# Servo_PCB.net
KiCad netlist of a schematic drawn in Altium Designer
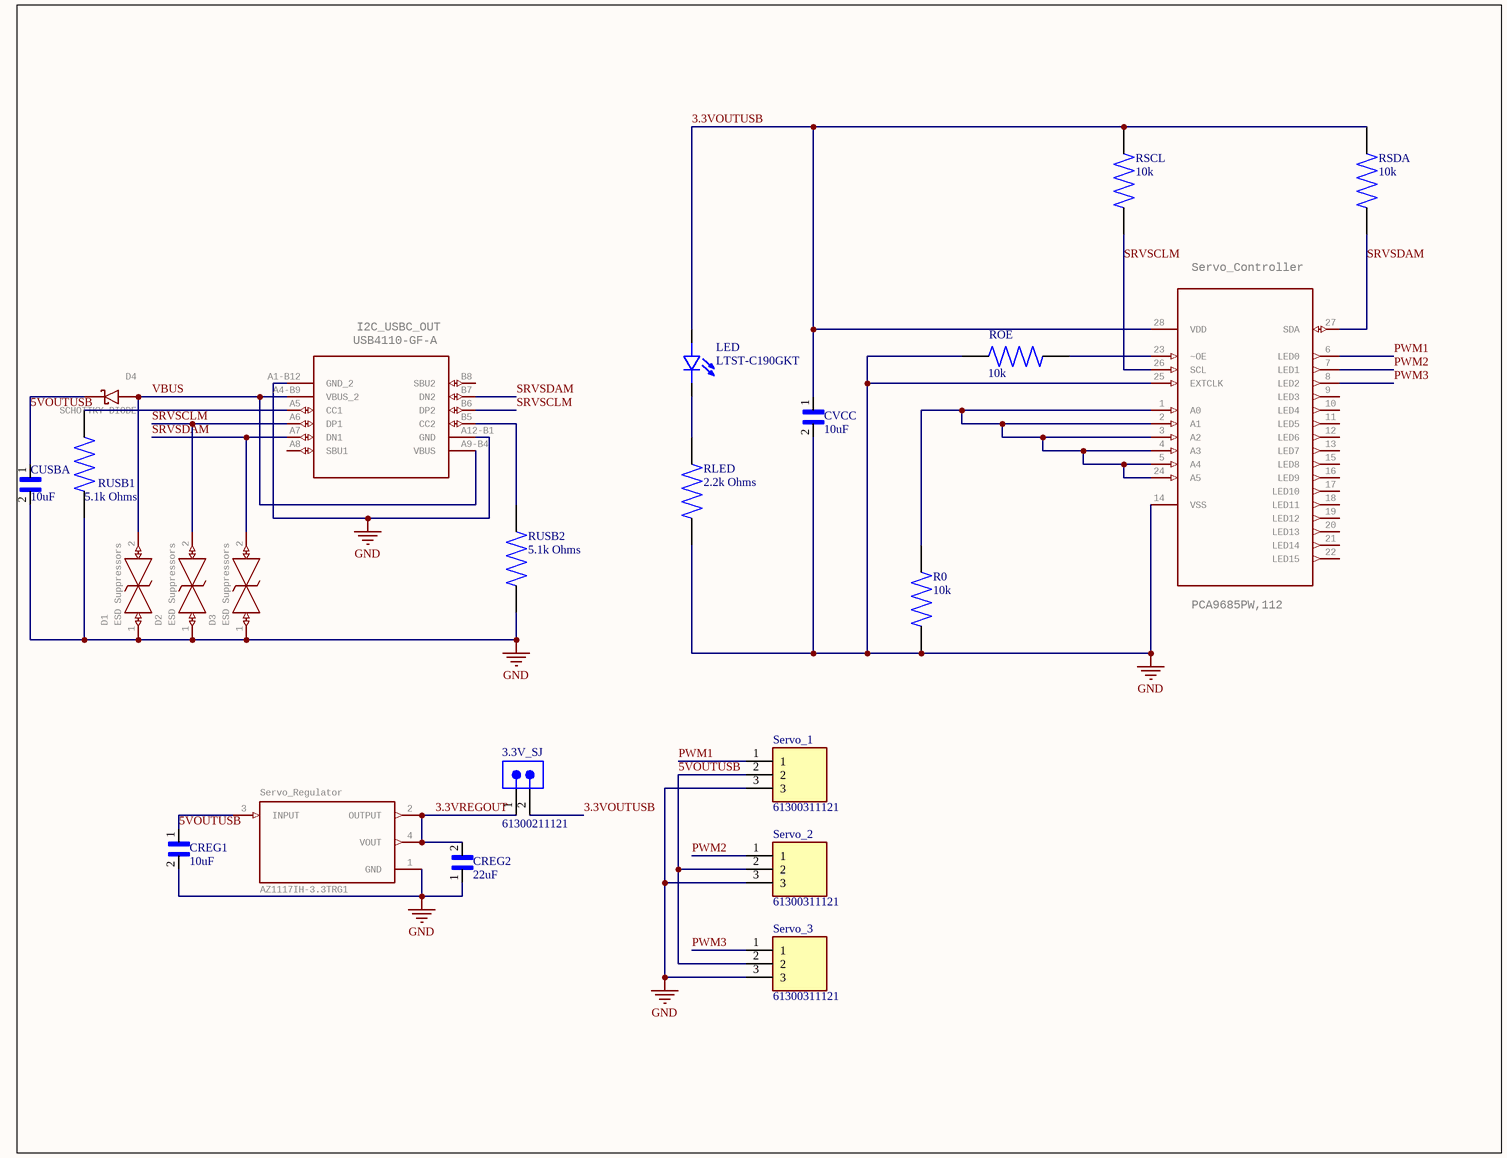
[diagram p0: Servo_PCB.SchDoc]

(export (version "E")
  (design (tool "Eeschema 10.0.6"))
  (components
    (comp (ref "3.3V_SJ")
      (value "61300211121")
      (footprint "61300211121")
      (description "CONN HEADER VERT 2POS 2.54MM")
      (libsource (lib "61300211121") (part "CMP-1712-00002-5"))
    )
    (comp (ref "CREG1")
      (value "10uF")
      (footprint "C0805C106J8RACAUTO.:CAPC2012X88N")
      (description "10ÂµF Â±5% 10V Ceramic Capacitor X7R 0805 _2012 Metric_")
      (fields (field (name "MP") "C0805C106J8RACAUTO") (field (name "MF") "KEMET"))
      (libsource (lib "C0805C106J8RACAUTO.") (part "C0805C106J8RACAUTO"))
    )
    (comp (ref "CREG2")
      (value "22uF")
      (footprint "GRM21BR61C226ME44L:CAPC2012X145N")
      (description "SMD Capacitor X5R(EIA) with Capacitance: 22uF Tol. 20%. Rated Voltage: 16Vdc")
      (fields (field (name "MP") "GRM21BR61C226ME44L") (field (name "MF") "Murata"))
      (libsource (lib "GRM21BR61C226ME44L") (part "GRM21BR61C226ME44L"))
    )
    (comp (ref "CUSBA")
      (value "10uF")
      (footprint "C0805C106J8RACAUTO.:CAPC2012X88N")
      (description "CAP CER 10UF 10V X7R 0805")
      (fields (field (name "MP") "C0805C106J8RACAUTO") (field (name "MF") "KEMET"))
      (libsource (lib "C0805C106J8RACAUTO.") (part "C0805C106J8RACAUTO"))
    )
    (comp (ref "CVCC")
      (value "10uF")
      (footprint "C0805C106J8RACAUTO.:CAPC2012X88N")
      (description "CAP CER 10UF 10V X7R 0805")
      (fields (field (name "MP") "C0805C106J8RACAUTO") (field (name "MF") "KEMET"))
      (libsource (lib "C0805C106J8RACAUTO.") (part "C0805C106J8RACAUTO"))
    )
    (comp (ref "D1")
      (value "ESD Suppressors")
      (footprint "MBTB-D-SOD-923F-IMP-0402")
      (description "TVS DIODE 5VWM 18.6V 0402/SOD923")
      (fields (field (name "MF") "Comchip Technology") (field (name "MP") "CPDQ5V0-HF"))
      (libsource (lib "CPDQ5V0-HF") (part "CPDQ5V0-HF"))
    )
    (comp (ref "D2")
      (value "ESD Suppressors")
      (footprint "MBTB-D-SOD-923F-IMP-0402")
      (description "TVS DIODE 5VWM 18.6V 0402/SOD923")
      (fields (field (name "MF") "Comchip Technology") (field (name "MP") "CPDQ5V0-HF"))
      (libsource (lib "CPDQ5V0-HF") (part "CPDQ5V0-HF"))
    )
    (comp (ref "D3")
      (value "ESD Suppressors")
      (footprint "MBTB-D-SOD-923F-IMP-0402")
      (description "TVS DIODE 5VWM 18.6V 0402/SOD923")
      (fields (field (name "MF") "Comchip Technology") (field (name "MP") "CPDQ5V0-HF"))
      (libsource (lib "CPDQ5V0-HF") (part "CPDQ5V0-HF"))
    )
    (comp (ref "D4")
      (value "SCHOTTKY DIODE")
      (footprint "SOD3715X145N")
      (description "DIODE SCHOTTKY 40V 1A SOD123")
      (fields (field (name "MF") "Diodes Inc.") (field (name "MP") "1N5819HW-7-F"))
      (libsource (lib "1N5819HW-7-F") (part "1N5819HW-7-F"))
    )
    (comp (ref "I2C_USBC_OUT")
      (value "USB4110-GF-A")
      (footprint "USB4110-GF-A_GCT")
      (description "CONN RCP USB2.0 TYP C 24P SMD RA")
      (fields (field (name "COPYRIGHT") "Copyright (C) 2023 Ultra Librarian. All rights reserved."))
      (libsource (lib "USB4110-GF-A") (part "USB4110-GF-A"))
    )
    (comp (ref "LED")
      (value "LTST-C190GKT")
      (footprint "LEDC1608X35N")
      (description "Green 569nm LED Indication - Discrete 2.1V 0603 (1608 Metric)")
      (fields (field (name "MF") "Lite-On Inc."))
      (libsource (lib "LEDC1608X35N") (part "LTST-C190GKT"))
    )
    (comp (ref "R0")
      (value "10k")
      (footprint "TNPW080510K0FEEA:RESC2012X55N")
      (description "RES 10K OHM 1% 1/8W 0805")
      (fields (field (name "MP") "TNPW080510K0FEEA"))
      (libsource (lib "TNPW080510K0FEEA") (part "TNPW080510K0FEEA"))
    )
    (comp (ref "RLED")
      (value "2.2k Ohms")
      (footprint "AC0805FR-072K2L:RESC2012X60N")
      (fields (field (name "MP") "AC0805FR-072K2L"))
      (libsource (lib "AC0805FR-072K2L") (part "AC0805FR-072K2L"))
    )
    (comp (ref "ROE")
      (value "10k")
      (footprint "TNPW080510K0FEEA:RESC2012X55N")
      (description "RES 10K OHM 1% 1/8W 0805")
      (fields (field (name "MP") "TNPW080510K0FEEA"))
      (libsource (lib "TNPW080510K0FEEA") (part "TNPW080510K0FEEA"))
    )
    (comp (ref "RSCL")
      (value "10k")
      (footprint "TNPW080510K0FEEA:RESC2012X55N")
      (description "RES 10K OHM 1% 1/8W 0805")
      (fields (field (name "MP") "TNPW080510K0FEEA"))
      (libsource (lib "TNPW080510K0FEEA") (part "TNPW080510K0FEEA"))
    )
    (comp (ref "RSDA")
      (value "10k")
      (footprint "TNPW080510K0FEEA:RESC2012X55N")
      (description "RES 10K OHM 1% 1/8W 0805")
      (fields (field (name "MP") "TNPW080510K0FEEA"))
      (libsource (lib "TNPW080510K0FEEA") (part "TNPW080510K0FEEA"))
    )
    (comp (ref "RUSB1")
      (value "5.1k Ohms")
      (footprint "RC0805JR-075K1L:RESC2012X60N")
      (description "RC0805 5,1K 5% 0,125W")
      (fields (field (name "MP") "RC0805JR-075K1L"))
      (libsource (lib "RC0805JR-075K1L") (part "RC0805JR-075K1L"))
    )
    (comp (ref "RUSB2")
      (value "5.1k Ohms")
      (footprint "RC0805JR-075K1L:RESC2012X60N")
      (description "RC0805 5,1K 5% 0,125W")
      (fields (field (name "MP") "RC0805JR-075K1L"))
      (libsource (lib "RC0805JR-075K1L") (part "RC0805JR-075K1L"))
    )
    (comp (ref "Servo_1")
      (value "61300311121")
      (footprint "HDRV3W64P0X254_1X3_762X254X869P")
      (description "CONN HEADER VERT 3POS 2.54MM")
      (fields (field (name "MOUSER PART NUMBER") "710-61300311121"))
      (libsource (lib "61300311121") (part "61300311121"))
    )
    (comp (ref "Servo_2")
      (value "61300311121")
      (footprint "HDRV3W64P0X254_1X3_762X254X869P")
      (description "Connector")
      (fields (field (name "MOUSER PART NUMBER") "710-61300311121"))
      (libsource (lib "61300311121") (part "61300311121"))
    )
    (comp (ref "Servo_3")
      (value "61300311121")
      (footprint "HDRV3W64P0X254_1X3_762X254X869P")
      (description "Connector")
      (fields (field (name "MOUSER PART NUMBER") "710-61300311121"))
      (libsource (lib "61300311121") (part "61300311121"))
    )
    (comp (ref "Servo_Controller")
      (value "PCA9685PW,112")
      (footprint "SOP65P640X110-28N")
      (description "IC LED DRVR LIN PWM 25MA 28TSSOP")
      (fields (field (name "MF") "NXP USA"))
      (libsource (lib "PCA9685PW_112") (part "PCA9685PW,112"))
    )
    (comp (ref "Servo_Regulator")
      (value "AZ1117IH-3.3TRG1")
      (footprint "SOT230P700X185-4N")
      (description "IC REG LINEAR 3.3V 1A SOT223")
      (fields (field (name "MF") "Diodes Inc."))
      (libsource (lib "AZ1117IH-3") (part "AZ1117IH-3.3TRG1"))
    )
  )
  (nets
    (net (code "1") (name "/3.3VOUTUSB") (class "Default")
      (node (ref "3.3V_SJ") (pin "2") (pinfunction "2_2") (pintype "passive"))
      (node (ref "CVCC") (pin "1") (pinfunction "1_1") (pintype "passive"))
      (node (ref "LED") (pin "A") (pinfunction "A_A") (pintype "passive"))
      (node (ref "RSCL") (pin "2") (pinfunction "2_2") (pintype "passive"))
      (node (ref "RSDA") (pin "2") (pinfunction "2_2") (pintype "passive"))
      (node (ref "Servo_Controller") (pin "28") (pinfunction "VDD_28") (pintype "power_in"))
    )
    (net (code "2") (name "/3.3VREGOUT") (class "Default")
      (node (ref "3.3V_SJ") (pin "1") (pinfunction "1_1") (pintype "passive"))
      (node (ref "CREG2") (pin "2") (pinfunction "2_2") (pintype "passive"))
      (node (ref "Servo_Regulator") (pin "2") (pinfunction "OUTPUT_2") (pintype "output"))
      (node (ref "Servo_Regulator") (pin "4") (pinfunction "VOUT_4") (pintype "output"))
    )
    (net (code "3") (name "/5VOUTUSB") (class "Default")
      (node (ref "CREG1") (pin "1") (pinfunction "1_1") (pintype "passive"))
      (node (ref "CUSBA") (pin "1") (pinfunction "1_1") (pintype "passive"))
      (node (ref "D4") (pin "C") (pinfunction "K_C") (pintype "passive"))
      (node (ref "Servo_1") (pin "2") (pinfunction "2_2") (pintype "passive"))
      (node (ref "Servo_2") (pin "2") (pinfunction "2_2") (pintype "passive"))
      (node (ref "Servo_3") (pin "2") (pinfunction "2_2") (pintype "passive"))
      (node (ref "Servo_Regulator") (pin "3") (pinfunction "INPUT_3") (pintype "input"))
    )
    (net (code "4") (name "/PWM1") (class "Default")
      (node (ref "Servo_1") (pin "1") (pinfunction "1_1") (pintype "passive"))
      (node (ref "Servo_Controller") (pin "6") (pinfunction "LED0_6") (pintype "output"))
    )
    (net (code "5") (name "/PWM2") (class "Default")
      (node (ref "Servo_2") (pin "1") (pinfunction "1_1") (pintype "passive"))
      (node (ref "Servo_Controller") (pin "7") (pinfunction "LED1_7") (pintype "output"))
    )
    (net (code "6") (name "/PWM3") (class "Default")
      (node (ref "Servo_3") (pin "1") (pinfunction "1_1") (pintype "passive"))
      (node (ref "Servo_Controller") (pin "8") (pinfunction "LED2_8") (pintype "output"))
    )
    (net (code "7") (name "/SRVSCLM") (class "Default")
      (node (ref "D2") (pin "2") (pinfunction "A_2") (pintype "bidirectional"))
      (node (ref "I2C_USBC_OUT") (pin "A6") (pinfunction "DP1_A6") (pintype "bidirectional"))
      (node (ref "I2C_USBC_OUT") (pin "B6") (pinfunction "DP2_B6") (pintype "bidirectional"))
      (node (ref "RSCL") (pin "1") (pinfunction "1_1") (pintype "passive"))
      (node (ref "Servo_Controller") (pin "26") (pinfunction "SCL_26") (pintype "input"))
    )
    (net (code "8") (name "/SRVSDAM") (class "Default")
      (node (ref "D3") (pin "2") (pinfunction "A_2") (pintype "bidirectional"))
      (node (ref "I2C_USBC_OUT") (pin "A7") (pinfunction "DN1_A7") (pintype "bidirectional"))
      (node (ref "I2C_USBC_OUT") (pin "B7") (pinfunction "DN2_B7") (pintype "bidirectional"))
      (node (ref "RSDA") (pin "1") (pinfunction "1_1") (pintype "passive"))
      (node (ref "Servo_Controller") (pin "27") (pinfunction "SDA_27") (pintype "bidirectional"))
    )
    (net (code "9") (name "/VBUS") (class "Default")
      (node (ref "D1") (pin "2") (pinfunction "A_2") (pintype "bidirectional"))
      (node (ref "D4") (pin "A") (pinfunction "A_A") (pintype "passive"))
      (node (ref "I2C_USBC_OUT") (pin "A4-B9") (pinfunction "VBUS_2_A4-B9") (pintype "power_in"))
      (node (ref "I2C_USBC_OUT") (pin "A9-B4") (pinfunction "VBUS_A9-B4") (pintype "power_in"))
    )
    (net (code "10") (name "GND") (class "Default")
      (node (ref "CREG1") (pin "2") (pinfunction "2_2") (pintype "passive"))
      (node (ref "CREG2") (pin "1") (pinfunction "1_1") (pintype "passive"))
      (node (ref "CUSBA") (pin "2") (pinfunction "2_2") (pintype "passive"))
      (node (ref "CVCC") (pin "2") (pinfunction "2_2") (pintype "passive"))
      (node (ref "D1") (pin "1") (pinfunction "K_1") (pintype "bidirectional"))
      (node (ref "D2") (pin "1") (pinfunction "K_1") (pintype "bidirectional"))
      (node (ref "D3") (pin "1") (pinfunction "K_1") (pintype "bidirectional"))
      (node (ref "I2C_USBC_OUT") (pin "A1-B12") (pinfunction "GND_2_A1-B12") (pintype "passive"))
      (node (ref "I2C_USBC_OUT") (pin "A12-B1") (pinfunction "GND_A12-B1") (pintype "passive"))
      (node (ref "R0") (pin "1") (pinfunction "1_1") (pintype "passive"))
      (node (ref "RLED") (pin "2") (pinfunction "2_2") (pintype "passive"))
      (node (ref "ROE") (pin "2") (pinfunction "2_2") (pintype "passive"))
      (node (ref "RUSB1") (pin "1") (pinfunction "1_1") (pintype "passive"))
      (node (ref "RUSB2") (pin "1") (pinfunction "1_1") (pintype "passive"))
      (node (ref "Servo_1") (pin "3") (pinfunction "3_3") (pintype "passive"))
      (node (ref "Servo_2") (pin "3") (pinfunction "3_3") (pintype "passive"))
      (node (ref "Servo_3") (pin "3") (pinfunction "3_3") (pintype "passive"))
      (node (ref "Servo_Controller") (pin "14") (pinfunction "VSS_14") (pintype "passive"))
      (node (ref "Servo_Controller") (pin "25") (pinfunction "EXTCLK_25") (pintype "input"))
      (node (ref "Servo_Regulator") (pin "1") (pinfunction "GND_1") (pintype "power_in"))
    )
    (net (code "11") (name "Net-(I2C_USBC_OUT-CC1)") (class "Default")
      (node (ref "I2C_USBC_OUT") (pin "A5") (pinfunction "CC1_A5") (pintype "bidirectional"))
      (node (ref "RUSB1") (pin "2") (pinfunction "2_2") (pintype "passive"))
    )
    (net (code "12") (name "Net-(I2C_USBC_OUT-CC2)") (class "Default")
      (node (ref "I2C_USBC_OUT") (pin "B5") (pinfunction "CC2_B5") (pintype "bidirectional"))
      (node (ref "RUSB2") (pin "2") (pinfunction "2_2") (pintype "passive"))
    )
    (net (code "13") (name "Net-(LED-PadC)") (class "Default")
      (node (ref "LED") (pin "C") (pinfunction "C_C") (pintype "passive"))
      (node (ref "RLED") (pin "1") (pinfunction "1_1") (pintype "passive"))
    )
    (net (code "14") (name "Net-(Servo_Controller-A0)") (class "Default")
      (node (ref "R0") (pin "2") (pinfunction "2_2") (pintype "passive"))
      (node (ref "Servo_Controller") (pin "1") (pinfunction "A0_1") (pintype "input"))
      (node (ref "Servo_Controller") (pin "2") (pinfunction "A1_2") (pintype "input"))
      (node (ref "Servo_Controller") (pin "24") (pinfunction "A5_24") (pintype "input"))
      (node (ref "Servo_Controller") (pin "3") (pinfunction "A2_3") (pintype "input"))
      (node (ref "Servo_Controller") (pin "4") (pinfunction "A3_4") (pintype "input"))
      (node (ref "Servo_Controller") (pin "5") (pinfunction "A4_5") (pintype "input"))
    )
    (net (code "15") (name "Net-(Servo_Controller-~OE)") (class "Default")
      (node (ref "ROE") (pin "1") (pinfunction "1_1") (pintype "passive"))
      (node (ref "Servo_Controller") (pin "23") (pinfunction "~OE_23") (pintype "input"))
    )
    (net (code "16") (name "unconnected-(I2C_USBC_OUT-SBU1-PadA8)") (class "Default")
      (node (ref "I2C_USBC_OUT") (pin "A8") (pinfunction "SBU1_A8") (pintype "bidirectional"))
    )
    (net (code "17") (name "unconnected-(I2C_USBC_OUT-SBU2-PadB8)") (class "Default")
      (node (ref "I2C_USBC_OUT") (pin "B8") (pinfunction "SBU2_B8") (pintype "bidirectional"))
    )
    (net (code "18") (name "unconnected-(Servo_Controller-LED3-Pad9)") (class "Default")
      (node (ref "Servo_Controller") (pin "9") (pinfunction "LED3_9") (pintype "output"))
    )
    (net (code "19") (name "unconnected-(Servo_Controller-LED4-Pad10)") (class "Default")
      (node (ref "Servo_Controller") (pin "10") (pinfunction "LED4_10") (pintype "output"))
    )
    (net (code "20") (name "unconnected-(Servo_Controller-LED5-Pad11)") (class "Default")
      (node (ref "Servo_Controller") (pin "11") (pinfunction "LED5_11") (pintype "output"))
    )
    (net (code "21") (name "unconnected-(Servo_Controller-LED6-Pad12)") (class "Default")
      (node (ref "Servo_Controller") (pin "12") (pinfunction "LED6_12") (pintype "output"))
    )
    (net (code "22") (name "unconnected-(Servo_Controller-LED7-Pad13)") (class "Default")
      (node (ref "Servo_Controller") (pin "13") (pinfunction "LED7_13") (pintype "output"))
    )
    (net (code "23") (name "unconnected-(Servo_Controller-LED8-Pad15)") (class "Default")
      (node (ref "Servo_Controller") (pin "15") (pinfunction "LED8_15") (pintype "output"))
    )
    (net (code "24") (name "unconnected-(Servo_Controller-LED9-Pad16)") (class "Default")
      (node (ref "Servo_Controller") (pin "16") (pinfunction "LED9_16") (pintype "output"))
    )
    (net (code "25") (name "unconnected-(Servo_Controller-LED10-Pad17)") (class "Default")
      (node (ref "Servo_Controller") (pin "17") (pinfunction "LED10_17") (pintype "output"))
    )
    (net (code "26") (name "unconnected-(Servo_Controller-LED11-Pad18)") (class "Default")
      (node (ref "Servo_Controller") (pin "18") (pinfunction "LED11_18") (pintype "output"))
    )
    (net (code "27") (name "unconnected-(Servo_Controller-LED12-Pad19)") (class "Default")
      (node (ref "Servo_Controller") (pin "19") (pinfunction "LED12_19") (pintype "output"))
    )
    (net (code "28") (name "unconnected-(Servo_Controller-LED13-Pad20)") (class "Default")
      (node (ref "Servo_Controller") (pin "20") (pinfunction "LED13_20") (pintype "output"))
    )
    (net (code "29") (name "unconnected-(Servo_Controller-LED14-Pad21)") (class "Default")
      (node (ref "Servo_Controller") (pin "21") (pinfunction "LED14_21") (pintype "output"))
    )
    (net (code "30") (name "unconnected-(Servo_Controller-LED15-Pad22)") (class "Default")
      (node (ref "Servo_Controller") (pin "22") (pinfunction "LED15_22") (pintype "output"))
    )
  )
)
